# esquematico.net
KiCad netlist of a schematic drawn in Altium Designer
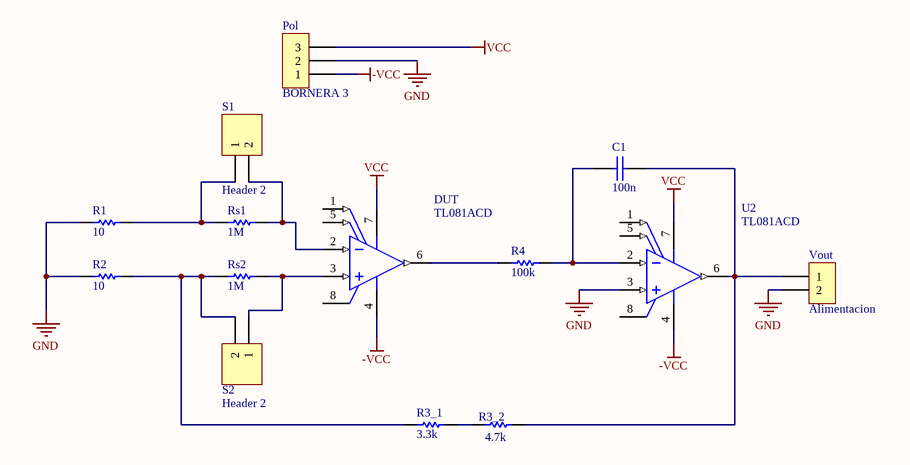
[diagram p0: esquematico.SchDoc]

(export (version "E")
  (design (tool "Eeschema 10.0.6"))
  (components
    (comp (ref "C1") (value "100n") (footprint "CAP200") (libsource (lib "LIBEBAL") (part "CAP")))
    (comp (ref "DUT")
      (value "TL081ACD")
      (footprint "DIP8")
      (fields (field (name "MANUFACTURER") "Texas Instruments"))
      (libsource (lib "TI Amplifiers and Linear Operational Amplifier General Purpose") (part "TL081ACD"))
    )
    (comp (ref "Pol")
      (value "BORNERA 3")
      (footprint "BORNERA3")
      (libsource (lib "LIB PIO IX") (part "BORNERA 3"))
    )
    (comp (ref "R1") (value "10") (footprint "RES300") (libsource (lib "LIB PIO IX") (part "RES")))
    (comp (ref "R2") (value "10") (footprint "RES300") (libsource (lib "LIB PIO IX") (part "RES")))
    (comp (ref "R3_1") (value "3.3k") (footprint "RES300") (libsource (lib "LIB PIO IX") (part "RES")))
    (comp (ref "R3_2") (value "4.7k") (footprint "RES300") (libsource (lib "LIB PIO IX") (part "RES")))
    (comp (ref "R4") (value "100k") (footprint "RES300") (libsource (lib "LIB PIO IX") (part "RES")))
    (comp (ref "Rs1") (value "1M") (footprint "RES300") (libsource (lib "LIB PIO IX") (part "RES")))
    (comp (ref "Rs2") (value "1M") (footprint "RES300") (libsource (lib "LIB PIO IX") (part "RES")))
    (comp (ref "S1")
      (value "Header 2")
      (footprint "HDR1X2")
      (description "Header, 2-Pin")
      (fields (field (name "PUBLISHER") "Altium Limited"))
      (libsource (lib "Miscellaneous Connectors") (part "Header 2"))
    )
    (comp (ref "S2")
      (value "Header 2")
      (footprint "HDR1X2")
      (description "Header, 2-Pin")
      (fields (field (name "PUBLISHER") "Altium Limited"))
      (libsource (lib "") (part "Header 2_1"))
    )
    (comp (ref "U2")
      (value "TL081ACD")
      (footprint "DIP8")
      (fields (field (name "MANUFACTURER") "Texas Instruments"))
      (libsource (lib "TI Amplifiers and Linear Operational Amplifier General Purpose") (part "TL081ACD"))
    )
    (comp (ref "Vout")
      (value "Alimentacion")
      (footprint "BORNERA2")
      (libsource (lib "LIBEBAL") (part "BORNERA 2"))
    )
  )
  (nets
    (net (code "1") (name "-VCC") (class "Default")
      (node (ref "DUT") (pin "4") (pinfunction "VCC-_4") (pintype "power_in"))
      (node (ref "Pol") (pin "1") (pinfunction "1_1") (pintype "passive"))
      (node (ref "U2") (pin "4") (pinfunction "VCC-_4") (pintype "power_in"))
    )
    (net (code "2") (name "GND") (class "Default")
      (node (ref "Pol") (pin "2") (pinfunction "2_2") (pintype "passive"))
      (node (ref "R1") (pin "1") (pinfunction "1_1") (pintype "passive"))
      (node (ref "R2") (pin "1") (pinfunction "1_1") (pintype "passive"))
      (node (ref "U2") (pin "3") (pinfunction "IN+_3") (pintype "input"))
      (node (ref "Vout") (pin "2") (pinfunction "2_2") (pintype "passive"))
    )
    (net (code "3") (name "Net-(DUT-IN+)") (class "Default")
      (node (ref "DUT") (pin "3") (pinfunction "IN+_3") (pintype "input"))
      (node (ref "Rs2") (pin "2") (pinfunction "2_2") (pintype "passive"))
      (node (ref "S2") (pin "1") (pinfunction "1_1") (pintype "passive"))
    )
    (net (code "4") (name "Net-(DUT-IN-)") (class "Default")
      (node (ref "DUT") (pin "2") (pinfunction "IN-_2") (pintype "input"))
      (node (ref "Rs1") (pin "2") (pinfunction "2_2") (pintype "passive"))
      (node (ref "S1") (pin "2") (pinfunction "2_2") (pintype "passive"))
    )
    (net (code "5") (name "Net-(DUT-OUT)") (class "Default")
      (node (ref "DUT") (pin "6") (pinfunction "OUT_6") (pintype "output"))
      (node (ref "R4") (pin "1") (pinfunction "1_1") (pintype "passive"))
    )
    (net (code "6") (name "Net-(R1-Pad2)") (class "Default")
      (node (ref "R1") (pin "2") (pinfunction "2_2") (pintype "passive"))
      (node (ref "Rs1") (pin "1") (pinfunction "1_1") (pintype "passive"))
      (node (ref "S1") (pin "1") (pinfunction "1_1") (pintype "passive"))
    )
    (net (code "7") (name "Net-(R2-Pad2)") (class "Default")
      (node (ref "R2") (pin "2") (pinfunction "2_2") (pintype "passive"))
      (node (ref "R3_1") (pin "1") (pinfunction "1_1") (pintype "passive"))
      (node (ref "Rs2") (pin "1") (pinfunction "1_1") (pintype "passive"))
      (node (ref "S2") (pin "2") (pinfunction "2_2") (pintype "passive"))
    )
    (net (code "8") (name "Net-(R3_1-Pad2)") (class "Default")
      (node (ref "R3_1") (pin "2") (pinfunction "2_2") (pintype "passive"))
      (node (ref "R3_2") (pin "1") (pinfunction "1_1") (pintype "passive"))
    )
    (net (code "9") (name "Net-(U2-IN-)") (class "Default")
      (node (ref "C1") (pin "1") (pinfunction "1_1") (pintype "passive"))
      (node (ref "R4") (pin "2") (pinfunction "2_2") (pintype "passive"))
      (node (ref "U2") (pin "2") (pinfunction "IN-_2") (pintype "input"))
    )
    (net (code "10") (name "Net-(U2-OUT)") (class "Default")
      (node (ref "C1") (pin "2") (pinfunction "2_2") (pintype "passive"))
      (node (ref "R3_2") (pin "2") (pinfunction "2_2") (pintype "passive"))
      (node (ref "U2") (pin "6") (pinfunction "OUT_6") (pintype "output"))
      (node (ref "Vout") (pin "1") (pinfunction "1_1") (pintype "passive"))
    )
    (net (code "11") (name "VCC") (class "Default")
      (node (ref "DUT") (pin "7") (pinfunction "VCC+_7") (pintype "power_in"))
      (node (ref "Pol") (pin "3") (pinfunction "3_3") (pintype "passive"))
      (node (ref "U2") (pin "7") (pinfunction "VCC+_7") (pintype "power_in"))
    )
    (net (code "12") (name "unconnected-(DUT-NC-Pad8)") (class "Default")
      (node (ref "DUT") (pin "8") (pinfunction "NC_8") (pintype "passive"))
    )
    (net (code "13") (name "unconnected-(DUT-OFFSET_N1-Pad1)") (class "Default")
      (node (ref "DUT") (pin "1") (pinfunction "OFFSET_N1_1") (pintype "input"))
    )
    (net (code "14") (name "unconnected-(DUT-OFFSET_N2-Pad5)") (class "Default")
      (node (ref "DUT") (pin "5") (pinfunction "OFFSET_N2_5") (pintype "input"))
    )
    (net (code "15") (name "unconnected-(U2-NC-Pad8)") (class "Default")
      (node (ref "U2") (pin "8") (pinfunction "NC_8") (pintype "passive"))
    )
    (net (code "16") (name "unconnected-(U2-OFFSET_N1-Pad1)") (class "Default")
      (node (ref "U2") (pin "1") (pinfunction "OFFSET_N1_1") (pintype "input"))
    )
    (net (code "17") (name "unconnected-(U2-OFFSET_N2-Pad5)") (class "Default")
      (node (ref "U2") (pin "5") (pinfunction "OFFSET_N2_5") (pintype "input"))
    )
  )
)
